# AudioCodec.net
KiCad netlist of a schematic drawn in Altium Designer
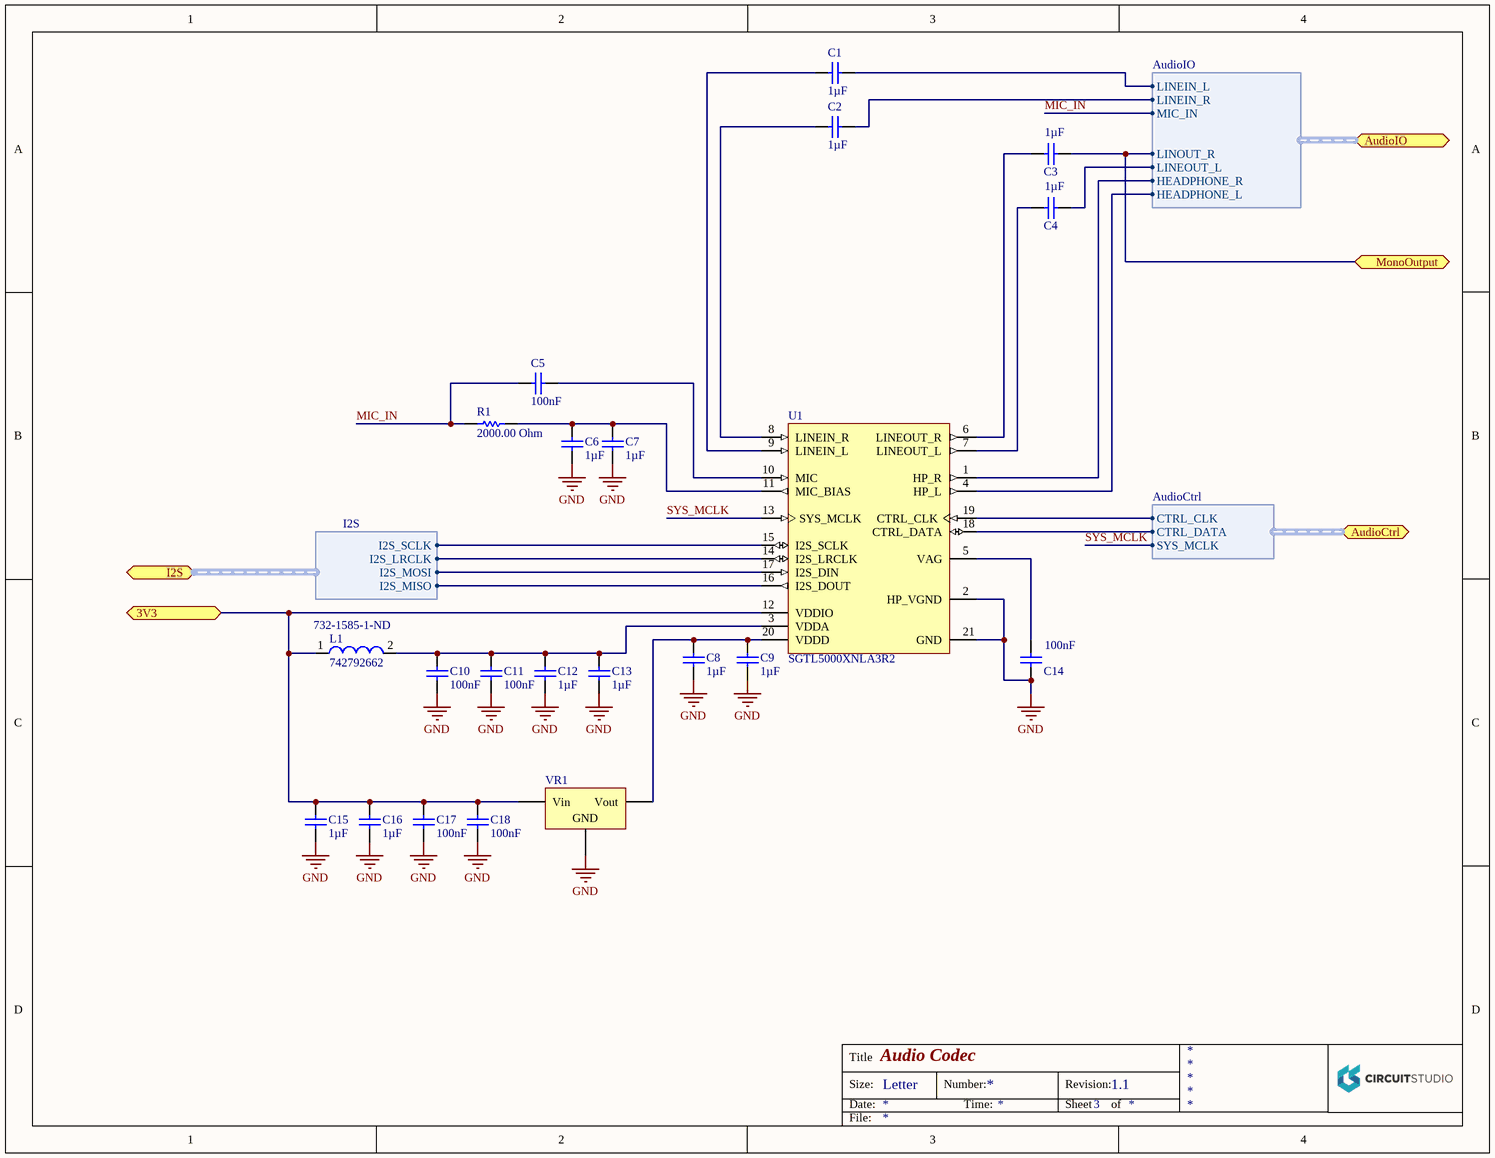
[diagram p0: AudioCodec.SchDoc]

(export (version "E")
  (design (tool "Eeschema 10.0.6"))
  (components
    (comp (ref "C1")
      (value "C1005X5R1C105K050BC")
      (footprint "CAPC1005X55X10ML05")
      (description "Chip Capacitor, 1 uF, +/- 10%, 16 V, -55 to 85 degC, 0402 (1005 Metric), RoHS, Tape and Reel")
      (fields
        (field (name "TOLERANCE") "±10%")
        (field (name "CAPACITANCE") "1µF")
        (field (name "PCN PART NUMBER") "MLCCPartNumberChange30/Nov/2012")
      )
      (libsource (lib "Altium Content Vault") (part "CMP-2000-05003-1"))
    )
    (comp (ref "C2")
      (value "C1005X5R1C105K050BC")
      (footprint "CAPC1005X55X10ML05")
      (description "Chip Capacitor, 1 uF, +/- 10%, 16 V, -55 to 85 degC, 0402 (1005 Metric), RoHS, Tape and Reel")
      (fields
        (field (name "TOLERANCE") "±10%")
        (field (name "CAPACITANCE") "1µF")
        (field (name "PCN PART NUMBER") "MLCCPartNumberChange30/Nov/2012")
      )
      (libsource (lib "Altium Content Vault") (part "CMP-2000-05003-1"))
    )
    (comp (ref "C3")
      (value "C1005X5R1C105K050BC")
      (footprint "CAPC1005X55X10ML05")
      (description "Chip Capacitor, 1 uF, +/- 10%, 16 V, -55 to 85 degC, 0402 (1005 Metric), RoHS, Tape and Reel")
      (fields
        (field (name "TOLERANCE") "±10%")
        (field (name "CAPACITANCE") "1µF")
        (field (name "PCN PART NUMBER") "MLCCPartNumberChange30/Nov/2012")
      )
      (libsource (lib "Altium Content Vault") (part "CMP-2000-05003-1"))
    )
    (comp (ref "C4")
      (value "C1005X5R1C105K050BC")
      (footprint "CAPC1005X55X10ML05")
      (description "Chip Capacitor, 1 uF, +/- 10%, 16 V, -55 to 85 degC, 0402 (1005 Metric), RoHS, Tape and Reel")
      (fields
        (field (name "TOLERANCE") "±10%")
        (field (name "CAPACITANCE") "1µF")
        (field (name "PCN PART NUMBER") "MLCCPartNumberChange30/Nov/2012")
      )
      (libsource (lib "Altium Content Vault") (part "CMP-2000-05003-1"))
    )
    (comp (ref "C5")
      (value "GRM155R71C104KA88D")
      (footprint "CAPC1005X55X25NL05T10")
      (description "Chip Capacitor, 0.1 uF, +/- 10%, 16 V, -55 to 125 degC, 0402 (1005 Metric), RoHS, Tape and Reel")
      (fields
        (field (name "VOLTAGE") "16V")
        (field (name "TOLERANCE") "10%")
        (field (name "CAPACITANCE") "100nF")
      )
      (libsource (lib "Altium Content Vault") (part "CMP-2100-03641-1"))
    )
    (comp (ref "C6")
      (value "C1005X5R1C105K050BC")
      (footprint "CAPC1005X55X10ML05")
      (description "Chip Capacitor, 1 uF, +/- 10%, 16 V, -55 to 85 degC, 0402 (1005 Metric), RoHS, Tape and Reel")
      (fields
        (field (name "TOLERANCE") "±10%")
        (field (name "CAPACITANCE") "1µF")
        (field (name "PCN PART NUMBER") "MLCCPartNumberChange30/Nov/2012")
      )
      (libsource (lib "Altium Content Vault") (part "CMP-2000-05003-1"))
    )
    (comp (ref "C7")
      (value "C1005X5R1C105K050BC")
      (footprint "CAPC1005X55X10ML05")
      (description "Chip Capacitor, 1 uF, +/- 10%, 16 V, -55 to 85 degC, 0402 (1005 Metric), RoHS, Tape and Reel")
      (fields
        (field (name "TOLERANCE") "±10%")
        (field (name "CAPACITANCE") "1µF")
        (field (name "PCN PART NUMBER") "MLCCPartNumberChange30/Nov/2012")
      )
      (libsource (lib "Altium Content Vault") (part "CMP-2000-05003-1"))
    )
    (comp (ref "C8")
      (value "C1005X5R1C105K050BC")
      (footprint "CAPC1005X55X10ML05")
      (description "Chip Capacitor, 1 uF, +/- 10%, 16 V, -55 to 85 degC, 0402 (1005 Metric), RoHS, Tape and Reel")
      (fields
        (field (name "TOLERANCE") "±10%")
        (field (name "CAPACITANCE") "1µF")
        (field (name "PCN PART NUMBER") "MLCCPartNumberChange30/Nov/2012")
      )
      (libsource (lib "Altium Content Vault") (part "CMP-2000-05003-1"))
    )
    (comp (ref "C9")
      (value "C1005X5R1C105K050BC")
      (footprint "CAPC1005X55X10ML05")
      (description "Chip Capacitor, 1 uF, +/- 10%, 16 V, -55 to 85 degC, 0402 (1005 Metric), RoHS, Tape and Reel")
      (fields
        (field (name "TOLERANCE") "±10%")
        (field (name "CAPACITANCE") "1µF")
        (field (name "PCN PART NUMBER") "MLCCPartNumberChange30/Nov/2012")
      )
      (libsource (lib "Altium Content Vault") (part "CMP-2000-05003-1"))
    )
    (comp (ref "C10")
      (value "GRM155R71C104KA88D")
      (footprint "CAPC1005X55X25NL05T10")
      (description "Chip Capacitor, 0.1 uF, +/- 10%, 16 V, -55 to 125 degC, 0402 (1005 Metric), RoHS, Tape and Reel")
      (fields
        (field (name "VOLTAGE") "16V")
        (field (name "TOLERANCE") "10%")
        (field (name "CAPACITANCE") "100nF")
      )
      (libsource (lib "Altium Content Vault") (part "CMP-2100-03641-1"))
    )
    (comp (ref "C11")
      (value "GRM155R71C104KA88D")
      (footprint "CAPC1005X55X25NL05T10")
      (description "Chip Capacitor, 0.1 uF, +/- 10%, 16 V, -55 to 125 degC, 0402 (1005 Metric), RoHS, Tape and Reel")
      (fields
        (field (name "VOLTAGE") "16V")
        (field (name "TOLERANCE") "10%")
        (field (name "CAPACITANCE") "100nF")
      )
      (libsource (lib "Altium Content Vault") (part "CMP-2100-03641-1"))
    )
    (comp (ref "C12")
      (value "C1005X5R1C105K050BC")
      (footprint "CAPC1005X55X10ML05")
      (description "Chip Capacitor, 1 uF, +/- 10%, 16 V, -55 to 85 degC, 0402 (1005 Metric), RoHS, Tape and Reel")
      (fields
        (field (name "TOLERANCE") "±10%")
        (field (name "CAPACITANCE") "1µF")
        (field (name "PCN PART NUMBER") "MLCCPartNumberChange30/Nov/2012")
      )
      (libsource (lib "Altium Content Vault") (part "CMP-2000-05003-1"))
    )
    (comp (ref "C13")
      (value "C1005X5R1C105K050BC")
      (footprint "CAPC1005X55X10ML05")
      (description "Chip Capacitor, 1 uF, +/- 10%, 16 V, -55 to 85 degC, 0402 (1005 Metric), RoHS, Tape and Reel")
      (fields
        (field (name "TOLERANCE") "±10%")
        (field (name "CAPACITANCE") "1µF")
        (field (name "PCN PART NUMBER") "MLCCPartNumberChange30/Nov/2012")
      )
      (libsource (lib "Altium Content Vault") (part "CMP-2000-05003-1"))
    )
    (comp (ref "C14")
      (value "GRM155R71C104KA88D")
      (footprint "CAPC1005X55X25NL05T10")
      (description "Chip Capacitor, 0.1 uF, +/- 10%, 16 V, -55 to 125 degC, 0402 (1005 Metric), RoHS, Tape and Reel")
      (fields
        (field (name "VOLTAGE") "16V")
        (field (name "TOLERANCE") "10%")
        (field (name "CAPACITANCE") "100nF")
      )
      (libsource (lib "Altium Content Vault") (part "CMP-2100-03641-1"))
    )
    (comp (ref "C15")
      (value "C1005X5R1C105K050BC")
      (footprint "CAPC1005X55X10ML05")
      (description "Chip Capacitor, 1 uF, +/- 10%, 16 V, -55 to 85 degC, 0402 (1005 Metric), RoHS, Tape and Reel")
      (fields
        (field (name "TOLERANCE") "±10%")
        (field (name "CAPACITANCE") "1µF")
        (field (name "PCN PART NUMBER") "MLCCPartNumberChange30/Nov/2012")
      )
      (libsource (lib "Altium Content Vault") (part "CMP-2000-05003-1"))
    )
    (comp (ref "C16")
      (value "C1005X5R1C105K050BC")
      (footprint "CAPC1005X55X10ML05")
      (description "Chip Capacitor, 1 uF, +/- 10%, 16 V, -55 to 85 degC, 0402 (1005 Metric), RoHS, Tape and Reel")
      (fields
        (field (name "TOLERANCE") "±10%")
        (field (name "CAPACITANCE") "1µF")
        (field (name "PCN PART NUMBER") "MLCCPartNumberChange30/Nov/2012")
      )
      (libsource (lib "Altium Content Vault") (part "CMP-2000-05003-1"))
    )
    (comp (ref "C17")
      (value "GRM155R71C104KA88D")
      (footprint "CAPC1005X55X25NL05T10")
      (description "Chip Capacitor, 0.1 uF, +/- 10%, 16 V, -55 to 125 degC, 0402 (1005 Metric), RoHS, Tape and Reel")
      (fields
        (field (name "VOLTAGE") "16V")
        (field (name "TOLERANCE") "10%")
        (field (name "CAPACITANCE") "100nF")
      )
      (libsource (lib "Altium Content Vault") (part "CMP-2100-03641-1"))
    )
    (comp (ref "C18")
      (value "GRM155R71C104KA88D")
      (footprint "CAPC1005X55X25NL05T10")
      (description "Chip Capacitor, 0.1 uF, +/- 10%, 16 V, -55 to 125 degC, 0402 (1005 Metric), RoHS, Tape and Reel")
      (fields
        (field (name "VOLTAGE") "16V")
        (field (name "TOLERANCE") "10%")
        (field (name "CAPACITANCE") "100nF")
      )
      (libsource (lib "Altium Content Vault") (part "CMP-2100-03641-1"))
    )
    (comp (ref "L1")
      (value "742792662")
      (footprint "SMD-0603")
      (description "SMD EMI Suppression Ferrite Bead WE-CBF, Z = 1000 Ohm")
      (fields (field (name "SUPPLIER PART NUMBER 1") "732-1585-1-ND"))
      (libsource (lib "Altium Content Vault") (part "PAS-IND-INDUCTOR-2"))
    )
    (comp (ref "R1")
      (value "2000.00 Ohm")
      (footprint "RESC0402(1005)_N")
      (description "2K 0.063W 5% 0402 (1005 Metric)  SMD")
      (fields (field (name "POWER") "0.063 W") (field (name "TOLERANCE") "5 %"))
      (libsource (lib "Altium Content Vault") (part "CMP-1011-00081-1"))
    )
    (comp (ref "U1")
      (value "SGTL5000XNLA3R2")
      (footprint "FRES-2032-01_L")
      (fields (field (name "MANUFACTURER") "Freescale Semiconductor"))
      (libsource (lib "Altium Content Vault") (part "FRES-SGTL5000-20"))
    )
    (comp (ref "VR1")
      (value "Volt Reg")
      (footprint "SOT23_L")
      (description "Voltage Regulator")
      (fields (field (name "PUBLISHER") "Altium Limited"))
      (libsource (lib "Miscellaneous Devices") (part "Volt Reg"))
    )
  )
  (nets
    (net (code "4") (name "/3V3") (class "Default")
      (node (ref "C15") (pin "1") (pinfunction "1_1") (pintype "passive"))
      (node (ref "C16") (pin "1") (pinfunction "1_1") (pintype "passive"))
      (node (ref "C17") (pin "1") (pinfunction "1_1") (pintype "passive"))
      (node (ref "C18") (pin "1") (pinfunction "1_1") (pintype "passive"))
      (node (ref "L1") (pin "1") (pinfunction "1_1") (pintype "passive"))
      (node (ref "U1") (pin "12") (pinfunction "VDDIO_12") (pintype "power_in"))
      (node (ref "VR1") (pin "1") (pinfunction "Vin_1") (pintype "passive"))
    )
    (net (code "5") (name "/CTRL_CLK") (class "Default")
      (node (ref "U1") (pin "19") (pinfunction "CTRL_CLK_19") (pintype "input"))
    )
    (net (code "6") (name "/CTRL_DATA") (class "Default")
      (node (ref "U1") (pin "18") (pinfunction "CTRL_DATA_18") (pintype "bidirectional"))
    )
    (net (code "7") (name "/HEADPHONE_L") (class "Default")
      (node (ref "U1") (pin "4") (pinfunction "HP_L_4") (pintype "output"))
    )
    (net (code "8") (name "/HEADPHONE_R") (class "Default")
      (node (ref "U1") (pin "1") (pinfunction "HP_R_1") (pintype "output"))
    )
    (net (code "9") (name "/I2S_LRCLK") (class "Default")
      (node (ref "U1") (pin "14") (pinfunction "I2S_LRCLK_14") (pintype "bidirectional"))
    )
    (net (code "10") (name "/I2S_MISO") (class "Default")
      (node (ref "U1") (pin "16") (pinfunction "I2S_DOUT_16") (pintype "output"))
    )
    (net (code "11") (name "/I2S_MOSI") (class "Default")
      (node (ref "U1") (pin "17") (pinfunction "I2S_DIN_17") (pintype "input"))
    )
    (net (code "12") (name "/I2S_SCLK") (class "Default")
      (node (ref "U1") (pin "15") (pinfunction "I2S_SCLK_15") (pintype "bidirectional"))
    )
    (net (code "13") (name "/LINEIN_L") (class "Default")
      (node (ref "C1") (pin "1") (pinfunction "1_1") (pintype "passive"))
    )
    (net (code "14") (name "/LINEIN_R") (class "Default")
      (node (ref "C2") (pin "1") (pinfunction "1_1") (pintype "passive"))
    )
    (net (code "15") (name "/LINEOUT_L") (class "Default")
      (node (ref "C4") (pin "1") (pinfunction "1_1") (pintype "passive"))
    )
    (net (code "16") (name "/MIC_IN") (class "Default")
      (node (ref "C5") (pin "2") (pinfunction "2_2") (pintype "passive"))
      (node (ref "R1") (pin "1") (pinfunction "1_1") (pintype "passive"))
    )
    (net (code "17") (name "/MonoOutput") (class "Default")
      (node (ref "C3") (pin "1") (pinfunction "1_1") (pintype "passive"))
    )
    (net (code "18") (name "/SYS_MCLK") (class "Default")
      (node (ref "U1") (pin "13") (pinfunction "SYS_MCLK_13") (pintype "input"))
    )
    (net (code "22") (name "GND") (class "Default")
      (node (ref "C10") (pin "2") (pinfunction "2_2") (pintype "passive"))
      (node (ref "C11") (pin "2") (pinfunction "2_2") (pintype "passive"))
      (node (ref "C12") (pin "2") (pinfunction "2_2") (pintype "passive"))
      (node (ref "C13") (pin "2") (pinfunction "2_2") (pintype "passive"))
      (node (ref "C14") (pin "1") (pinfunction "1_1") (pintype "passive"))
      (node (ref "C15") (pin "2") (pinfunction "2_2") (pintype "passive"))
      (node (ref "C16") (pin "2") (pinfunction "2_2") (pintype "passive"))
      (node (ref "C17") (pin "2") (pinfunction "2_2") (pintype "passive"))
      (node (ref "C18") (pin "2") (pinfunction "2_2") (pintype "passive"))
      (node (ref "C6") (pin "2") (pinfunction "2_2") (pintype "passive"))
      (node (ref "C7") (pin "2") (pinfunction "2_2") (pintype "passive"))
      (node (ref "C8") (pin "2") (pinfunction "2_2") (pintype "passive"))
      (node (ref "C9") (pin "2") (pinfunction "2_2") (pintype "passive"))
      (node (ref "U1") (pin "2") (pinfunction "HP_VGND_2") (pintype "power_in"))
      (node (ref "U1") (pin "21") (pinfunction "GND_21") (pintype "power_in"))
      (node (ref "VR1") (pin "2") (pinfunction "GND_2") (pintype "passive"))
    )
    (net (code "23") (name "Net-(U1-LINEIN_L)") (class "Default")
      (node (ref "C1") (pin "2") (pinfunction "2_2") (pintype "passive"))
      (node (ref "U1") (pin "9") (pinfunction "LINEIN_L_9") (pintype "input"))
    )
    (net (code "24") (name "Net-(U1-LINEIN_R)") (class "Default")
      (node (ref "C2") (pin "2") (pinfunction "2_2") (pintype "passive"))
      (node (ref "U1") (pin "8") (pinfunction "LINEIN_R_8") (pintype "input"))
    )
    (net (code "25") (name "Net-(U1-LINEOUT_L)") (class "Default")
      (node (ref "C4") (pin "2") (pinfunction "2_2") (pintype "passive"))
      (node (ref "U1") (pin "7") (pinfunction "LINEOUT_L_7") (pintype "output"))
    )
    (net (code "26") (name "Net-(U1-LINEOUT_R)") (class "Default")
      (node (ref "C3") (pin "2") (pinfunction "2_2") (pintype "passive"))
      (node (ref "U1") (pin "6") (pinfunction "LINEOUT_R_6") (pintype "output"))
    )
    (net (code "27") (name "Net-(U1-MIC)") (class "Default")
      (node (ref "C5") (pin "1") (pinfunction "1_1") (pintype "passive"))
      (node (ref "U1") (pin "10") (pinfunction "MIC_10") (pintype "input"))
    )
    (net (code "28") (name "Net-(U1-MIC_BIAS)") (class "Default")
      (node (ref "C6") (pin "1") (pinfunction "1_1") (pintype "passive"))
      (node (ref "C7") (pin "1") (pinfunction "1_1") (pintype "passive"))
      (node (ref "R1") (pin "2") (pinfunction "2_2") (pintype "passive"))
      (node (ref "U1") (pin "11") (pinfunction "MIC_BIAS_11") (pintype "output"))
    )
    (net (code "29") (name "Net-(U1-VAG)") (class "Default")
      (node (ref "C14") (pin "2") (pinfunction "2_2") (pintype "passive"))
      (node (ref "U1") (pin "5") (pinfunction "VAG_5") (pintype "passive"))
    )
    (net (code "30") (name "Net-(U1-VDDA)") (class "Default")
      (node (ref "C10") (pin "1") (pinfunction "1_1") (pintype "passive"))
      (node (ref "C11") (pin "1") (pinfunction "1_1") (pintype "passive"))
      (node (ref "C12") (pin "1") (pinfunction "1_1") (pintype "passive"))
      (node (ref "C13") (pin "1") (pinfunction "1_1") (pintype "passive"))
      (node (ref "L1") (pin "2") (pinfunction "2_2") (pintype "passive"))
      (node (ref "U1") (pin "3") (pinfunction "VDDA_3") (pintype "power_in"))
    )
    (net (code "31") (name "Net-(U1-VDDD)") (class "Default")
      (node (ref "C8") (pin "1") (pinfunction "1_1") (pintype "passive"))
      (node (ref "C9") (pin "1") (pinfunction "1_1") (pintype "passive"))
      (node (ref "U1") (pin "20") (pinfunction "VDDD_20") (pintype "power_in"))
      (node (ref "VR1") (pin "3") (pinfunction "Vout_3") (pintype "passive"))
    )
  )
)
